# rf_switch.net
KiCad netlist of a schematic drawn in EAGLE
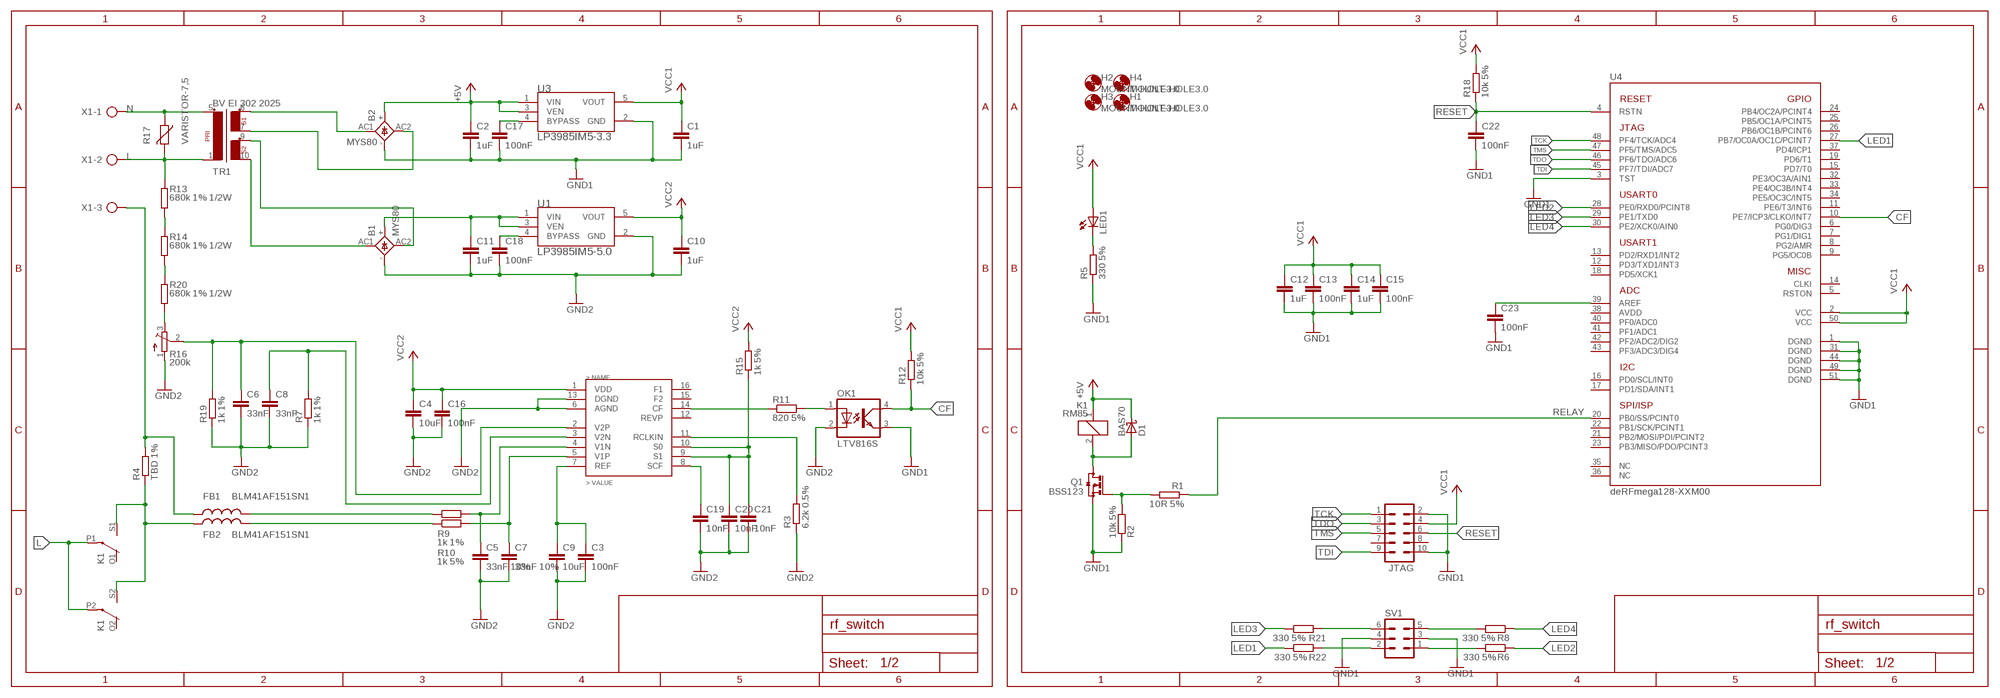
[diagram p0: schematic, sheet 1]

(export (version "E")
  (design (tool "Eeschema 10.0.6"))
  (components
    (comp (ref "B1")
      (value "MYS80")
      (footprint "eagle-import:MICRODIL")
      (libsource (lib "eagle-import") (part "MYS80"))
    )
    (comp (ref "B2")
      (value "MYS80")
      (footprint "eagle-import:MICRODIL")
      (libsource (lib "eagle-import") (part "MYS80"))
    )
    (comp (ref "C1")
      (value "1uF")
      (footprint "eagle-import:C0603")
      (libsource (lib "eagle-import") (part "C-EUC0603"))
    )
    (comp (ref "C2")
      (value "1uF")
      (footprint "eagle-import:C0603")
      (libsource (lib "eagle-import") (part "C-EUC0603"))
    )
    (comp (ref "C3")
      (value "100nF")
      (footprint "eagle-import:C0603")
      (libsource (lib "eagle-import") (part "C-EUC0603"))
    )
    (comp (ref "C4")
      (value "10uF")
      (footprint "eagle-import:C0805")
      (libsource (lib "eagle-import") (part "C-EUC0805"))
    )
    (comp (ref "C5")
      (value "33nF 10%")
      (footprint "eagle-import:C0805")
      (libsource (lib "eagle-import") (part "C-EUC0805"))
    )
    (comp (ref "C6")
      (value "33nF")
      (footprint "eagle-import:C0603")
      (libsource (lib "eagle-import") (part "C-EUC0603"))
    )
    (comp (ref "C7")
      (value "33nF 10%")
      (footprint "eagle-import:C0805")
      (libsource (lib "eagle-import") (part "C-EUC0805"))
    )
    (comp (ref "C8")
      (value "33nF")
      (footprint "eagle-import:C0603")
      (libsource (lib "eagle-import") (part "C-EUC0603"))
    )
    (comp (ref "C9")
      (value "10uF")
      (footprint "eagle-import:C0805")
      (libsource (lib "eagle-import") (part "C-EUC0805"))
    )
    (comp (ref "C10")
      (value "1uF")
      (footprint "eagle-import:C0603")
      (libsource (lib "eagle-import") (part "C-EUC0603"))
    )
    (comp (ref "C11")
      (value "1uF")
      (footprint "eagle-import:C0603")
      (libsource (lib "eagle-import") (part "C-EUC0603"))
    )
    (comp (ref "C12")
      (value "1uF")
      (footprint "eagle-import:C0603")
      (libsource (lib "eagle-import") (part "C-EUC0603"))
    )
    (comp (ref "C13")
      (value "100nF")
      (footprint "eagle-import:C0603")
      (libsource (lib "eagle-import") (part "C-EUC0603"))
    )
    (comp (ref "C14")
      (value "1uF")
      (footprint "eagle-import:C0603")
      (libsource (lib "eagle-import") (part "C-EUC0603"))
    )
    (comp (ref "C15")
      (value "100nF")
      (footprint "eagle-import:C0603")
      (libsource (lib "eagle-import") (part "C-EUC0603"))
    )
    (comp (ref "C16")
      (value "100nF")
      (footprint "eagle-import:C0603")
      (libsource (lib "eagle-import") (part "C-EUC0603"))
    )
    (comp (ref "C17")
      (value "100nF")
      (footprint "eagle-import:C0603")
      (libsource (lib "eagle-import") (part "C-EUC0603"))
    )
    (comp (ref "C18")
      (value "100nF")
      (footprint "eagle-import:C0603")
      (libsource (lib "eagle-import") (part "C-EUC0603"))
    )
    (comp (ref "C19")
      (value "10nF")
      (footprint "eagle-import:C0603")
      (libsource (lib "eagle-import") (part "C-EUC0603"))
    )
    (comp (ref "C20")
      (value "10nF")
      (footprint "eagle-import:C0603")
      (libsource (lib "eagle-import") (part "C-EUC0603"))
    )
    (comp (ref "C21")
      (value "10nF")
      (footprint "eagle-import:C0603")
      (libsource (lib "eagle-import") (part "C-EUC0603"))
    )
    (comp (ref "C22")
      (value "100nF")
      (footprint "eagle-import:C0603")
      (libsource (lib "eagle-import") (part "C-EUC0603"))
    )
    (comp (ref "C23")
      (value "100nF")
      (footprint "eagle-import:C0603")
      (libsource (lib "eagle-import") (part "C-EUC0603"))
    )
    (comp (ref "D1")
      (value "BAS70")
      (footprint "eagle-import:SOT23")
      (libsource (lib "eagle-import") (part "BAS70"))
    )
    (comp (ref "FB1")
      (value "BLM41AF151SN1")
      (footprint "eagle-import:1806")
      (libsource (lib "eagle-import") (part "FERRITE-BEAD"))
    )
    (comp (ref "FB2")
      (value "BLM41AF151SN1")
      (footprint "eagle-import:1806")
      (libsource (lib "eagle-import") (part "FERRITE-BEAD"))
    )
    (comp (ref "H1")
      (value "MOUNT-HOLE3.0")
      (footprint "eagle-import:3,0")
      (libsource (lib "eagle-import") (part "MOUNT-HOLE3.0"))
    )
    (comp (ref "H2")
      (value "MOUNT-HOLE3.0")
      (footprint "eagle-import:3,0")
      (libsource (lib "eagle-import") (part "MOUNT-HOLE3.0"))
    )
    (comp (ref "H3")
      (value "MOUNT-HOLE3.0")
      (footprint "eagle-import:3,0")
      (libsource (lib "eagle-import") (part "MOUNT-HOLE3.0"))
    )
    (comp (ref "H4")
      (value "MOUNT-HOLE3.0")
      (footprint "eagle-import:3,0")
      (libsource (lib "eagle-import") (part "MOUNT-HOLE3.0"))
    )
    (comp (ref "JTAG")
      (value "MA05-2")
      (footprint "eagle-import:MA05-2")
      (libsource (lib "eagle-import") (part "MA05-2"))
    )
    (comp (ref "K1")
      (value "RM85")
      (footprint "eagle-import:F4052")
      (libsource (lib "eagle-import") (part "4052"))
    )
    (comp (ref "LED1")
      (value "LEDSML0603")
      (footprint "eagle-import:SML0603")
      (libsource (lib "eagle-import") (part "LEDSML0603"))
    )
    (comp (ref "OK1")
      (value "LTV816S")
      (footprint "eagle-import:SMD4")
      (libsource (lib "eagle-import") (part "LTV816S"))
    )
    (comp (ref "Q1")
      (value "BSS123")
      (footprint "eagle-import:SOT23")
      (libsource (lib "eagle-import") (part "BSS123"))
    )
    (comp (ref "R1")
      (value "10R 5%")
      (footprint "eagle-import:R0603")
      (libsource (lib "eagle-import") (part "R-EU_R0603"))
    )
    (comp (ref "R2")
      (value "10k 5%")
      (footprint "eagle-import:R0603")
      (libsource (lib "eagle-import") (part "R-EU_R0603"))
    )
    (comp (ref "R3")
      (value "6.2k 0.5%")
      (footprint "eagle-import:R0603")
      (libsource (lib "eagle-import") (part "R-EU_R0603"))
    )
    (comp (ref "R4")
      (value "TBD 1%")
      (footprint "eagle-import:R1206")
      (libsource (lib "eagle-import") (part "R-EU_R1206"))
    )
    (comp (ref "R5")
      (value "330 5%")
      (footprint "eagle-import:R0603")
      (libsource (lib "eagle-import") (part "R-EU_R0603"))
    )
    (comp (ref "R6")
      (value "330 5%")
      (footprint "eagle-import:R0603")
      (libsource (lib "eagle-import") (part "R-EU_R0603"))
    )
    (comp (ref "R7")
      (value "1k 1%")
      (footprint "eagle-import:R0603")
      (libsource (lib "eagle-import") (part "R-EU_R0603"))
    )
    (comp (ref "R8")
      (value "330 5%")
      (footprint "eagle-import:R0603")
      (libsource (lib "eagle-import") (part "R-EU_R0603"))
    )
    (comp (ref "R9")
      (value "1k 1%")
      (footprint "eagle-import:R1206")
      (libsource (lib "eagle-import") (part "R-EU_R1206"))
    )
    (comp (ref "R10")
      (value "1k 5%")
      (footprint "eagle-import:R1206")
      (libsource (lib "eagle-import") (part "R-EU_R1206"))
    )
    (comp (ref "R11")
      (value "820 5%")
      (footprint "eagle-import:R0603")
      (libsource (lib "eagle-import") (part "R-EU_R0603"))
    )
    (comp (ref "R12")
      (value "10k 5%")
      (footprint "eagle-import:R0603")
      (libsource (lib "eagle-import") (part "R-EU_R0603"))
    )
    (comp (ref "R13")
      (value "680k 1% 1/2W")
      (footprint "eagle-import:R1206")
      (libsource (lib "eagle-import") (part "R-EU_R1206"))
    )
    (comp (ref "R14")
      (value "680k 1% 1/2W")
      (footprint "eagle-import:R1206")
      (libsource (lib "eagle-import") (part "R-EU_R1206"))
    )
    (comp (ref "R15")
      (value "1k 5%")
      (footprint "eagle-import:R0603")
      (libsource (lib "eagle-import") (part "R-EU_R0603"))
    )
    (comp (ref "R16")
      (value "200k")
      (footprint "eagle-import:3223W")
      (libsource (lib "eagle-import") (part "TRIM_EU-3223W"))
    )
    (comp (ref "R17")
      (value "VARISTOR-7,5")
      (footprint "eagle-import:R-7,5")
      (libsource (lib "eagle-import") (part "VARISTOR-7,5"))
    )
    (comp (ref "R18")
      (value "10k 5%")
      (footprint "eagle-import:R0603")
      (libsource (lib "eagle-import") (part "R-EU_R0603"))
    )
    (comp (ref "R19")
      (value "1k 1%")
      (footprint "eagle-import:R0603")
      (libsource (lib "eagle-import") (part "R-EU_R0603"))
    )
    (comp (ref "R20")
      (value "680k 1% 1/2W")
      (footprint "eagle-import:R1206")
      (libsource (lib "eagle-import") (part "R-EU_R1206"))
    )
    (comp (ref "R21")
      (value "330 5%")
      (footprint "eagle-import:R0603")
      (libsource (lib "eagle-import") (part "R-EU_R0603"))
    )
    (comp (ref "R22")
      (value "330 5%")
      (footprint "eagle-import:R0603")
      (libsource (lib "eagle-import") (part "R-EU_R0603"))
    )
    (comp (ref "SV1")
      (value "MA03-2")
      (footprint "eagle-import:MA03-2")
      (libsource (lib "eagle-import") (part "MA03-2"))
    )
    (comp (ref "TR1")
      (value "BV EI 302 2025")
      (footprint "eagle-import:EI30-2")
      (libsource (lib "eagle-import") (part "EI30-2"))
    )
    (comp (ref "U1")
      (value "LP3985IM5-5.0")
      (footprint "eagle-import:SOT95P300X120-5N")
      (fields (field (name "MPN") "LP3985IM5-3.3"))
      (libsource (lib "eagle-import") (part "LP3985IM5-3.3"))
    )
    (comp (ref "U2")
      (value "ADE7757")
      (footprint "eagle-import:SOIC-16")
      (libsource (lib "eagle-import") (part "ADE7757"))
    )
    (comp (ref "U3")
      (value "LP3985IM5-3.3")
      (footprint "eagle-import:SOT95P300X120-5N")
      (libsource (lib "eagle-import") (part "LP3985IM5-3.3"))
    )
    (comp (ref "U4")
      (value "DERFMEGA128-XXM00")
      (footprint "eagle-import:A-M00")
      (libsource (lib "eagle-import") (part "DERFMEGA128-XXM00"))
    )
    (comp (ref "X1")
      (value "AK500/3")
      (footprint "eagle-import:AK500_3")
      (libsource (lib "eagle-import") (part "AK500/3"))
    )
  )
  (nets
    (net (code "1") (name "+5V") (class "Default")
      (node (ref "B2") (pin "+") (pinfunction "+_+") (pintype "passive"))
      (node (ref "C2") (pin "1") (pinfunction "1_1") (pintype "passive"))
      (node (ref "D1") (pin "3") (pinfunction "C_3") (pintype "passive"))
      (node (ref "K1") (pin "1") (pinfunction "1_1") (pintype "passive"))
      (node (ref "U3") (pin "1") (pinfunction "VIN_1") (pintype "power_in"))
      (node (ref "U3") (pin "3") (pinfunction "VEN_3") (pintype "input"))
    )
    (net (code "2") (name "AVDD") (class "Default")
      (node (ref "U4") (pin "38") (pinfunction "AVDD_38") (pintype "power_in"))
    )
    (net (code "3") (name "CF") (class "Default")
      (node (ref "OK1") (pin "4") (pinfunction "COL_4") (pintype "passive"))
      (node (ref "R12") (pin "1") (pinfunction "1_1") (pintype "passive"))
      (node (ref "U4") (pin "10") (pinfunction "PE7/ICP3/CLKO/INT7_10") (pintype "bidirectional"))
    )
    (net (code "4") (name "GND1") (class "Default")
      (node (ref "B2") (pin "-") (pinfunction "-_-") (pintype "passive"))
      (node (ref "C1") (pin "2") (pinfunction "2_2") (pintype "passive"))
      (node (ref "C12") (pin "2") (pinfunction "2_2") (pintype "passive"))
      (node (ref "C13") (pin "2") (pinfunction "2_2") (pintype "passive"))
      (node (ref "C14") (pin "2") (pinfunction "2_2") (pintype "passive"))
      (node (ref "C15") (pin "2") (pinfunction "2_2") (pintype "passive"))
      (node (ref "C17") (pin "2") (pinfunction "2_2") (pintype "passive"))
      (node (ref "C2") (pin "2") (pinfunction "2_2") (pintype "passive"))
      (node (ref "C22") (pin "2") (pinfunction "2_2") (pintype "passive"))
      (node (ref "C23") (pin "2") (pinfunction "2_2") (pintype "passive"))
      (node (ref "JTAG") (pin "10") (pinfunction "10_10") (pintype "passive"))
      (node (ref "JTAG") (pin "2") (pinfunction "2_2") (pintype "passive"))
      (node (ref "OK1") (pin "3") (pinfunction "EMIT_3") (pintype "passive"))
      (node (ref "Q1") (pin "2") (pinfunction "S_2") (pintype "passive"))
      (node (ref "R2") (pin "1") (pinfunction "1_1") (pintype "passive"))
      (node (ref "R5") (pin "1") (pinfunction "1_1") (pintype "passive"))
      (node (ref "SV1") (pin "3") (pinfunction "3_3") (pintype "passive"))
      (node (ref "SV1") (pin "4") (pinfunction "4_4") (pintype "passive"))
      (node (ref "U3") (pin "2") (pinfunction "GND_2") (pintype "passive"))
      (node (ref "U4") (pin "1") (pinfunction "DGND_1") (pintype "power_in"))
      (node (ref "U4") (pin "3") (pinfunction "TST_3") (pintype "bidirectional"))
      (node (ref "U4") (pin "31") (pinfunction "DGND_31") (pintype "power_in"))
      (node (ref "U4") (pin "44") (pinfunction "DGND_44") (pintype "power_in"))
      (node (ref "U4") (pin "49") (pinfunction "DGND_49") (pintype "power_in"))
      (node (ref "U4") (pin "51") (pinfunction "DGND_51") (pintype "power_in"))
    )
    (net (code "5") (name "GND2") (class "Default")
      (node (ref "B1") (pin "-") (pinfunction "-_-") (pintype "passive"))
      (node (ref "C10") (pin "2") (pinfunction "2_2") (pintype "passive"))
      (node (ref "C11") (pin "2") (pinfunction "2_2") (pintype "passive"))
      (node (ref "C16") (pin "2") (pinfunction "2_2") (pintype "passive"))
      (node (ref "C18") (pin "2") (pinfunction "2_2") (pintype "passive"))
      (node (ref "C19") (pin "2") (pinfunction "2_2") (pintype "passive"))
      (node (ref "C20") (pin "2") (pinfunction "2_2") (pintype "passive"))
      (node (ref "C21") (pin "2") (pinfunction "2_2") (pintype "passive"))
      (node (ref "C3") (pin "2") (pinfunction "2_2") (pintype "passive"))
      (node (ref "C4") (pin "2") (pinfunction "2_2") (pintype "passive"))
      (node (ref "C5") (pin "2") (pinfunction "2_2") (pintype "passive"))
      (node (ref "C6") (pin "2") (pinfunction "2_2") (pintype "passive"))
      (node (ref "C7") (pin "2") (pinfunction "2_2") (pintype "passive"))
      (node (ref "C8") (pin "2") (pinfunction "2_2") (pintype "passive"))
      (node (ref "C9") (pin "2") (pinfunction "2_2") (pintype "passive"))
      (node (ref "OK1") (pin "2") (pinfunction "C_2") (pintype "passive"))
      (node (ref "R16") (pin "1") (pinfunction "A_1") (pintype "passive"))
      (node (ref "R19") (pin "1") (pinfunction "1_1") (pintype "passive"))
      (node (ref "R3") (pin "1") (pinfunction "1_1") (pintype "passive"))
      (node (ref "R7") (pin "1") (pinfunction "1_1") (pintype "passive"))
      (node (ref "U1") (pin "2") (pinfunction "GND_2") (pintype "passive"))
      (node (ref "U2") (pin "13") (pinfunction "DGND_13") (pintype "power_in"))
      (node (ref "U2") (pin "6") (pinfunction "AGND_6") (pintype "power_in"))
    )
    (net (code "6") (name "L") (class "Default")
      (node (ref "K1") (pin "P1") (pinfunction "P_P1") (pintype "passive"))
      (node (ref "K1") (pin "P2") (pinfunction "P_P2") (pintype "passive"))
      (node (ref "R13") (pin "1") (pinfunction "1_1") (pintype "passive"))
      (node (ref "R17") (pin "2") (pinfunction "2_2") (pintype "passive"))
      (node (ref "TR1") (pin "1") (pinfunction "1_1") (pintype "passive"))
      (node (ref "X1") (pin "2") (pinfunction "KL_2") (pintype "passive"))
    )
    (net (code "7") (name "LED1") (class "Default")
      (node (ref "R22") (pin "1") (pinfunction "1_1") (pintype "passive"))
      (node (ref "U4") (pin "27") (pinfunction "PB7/OC0A/OC1C/PCINT7_27") (pintype "bidirectional"))
    )
    (net (code "8") (name "LED2") (class "Default")
      (node (ref "R6") (pin "1") (pinfunction "1_1") (pintype "passive"))
      (node (ref "U4") (pin "28") (pinfunction "PE0/RXD0/PCINT8_28") (pintype "bidirectional"))
    )
    (net (code "9") (name "LED3") (class "Default")
      (node (ref "R21") (pin "1") (pinfunction "1_1") (pintype "passive"))
      (node (ref "U4") (pin "29") (pinfunction "PE1/TXD0_29") (pintype "bidirectional"))
    )
    (net (code "10") (name "LED4") (class "Default")
      (node (ref "R8") (pin "1") (pinfunction "1_1") (pintype "passive"))
      (node (ref "U4") (pin "30") (pinfunction "PE2/XCK0/AIN0_30") (pintype "bidirectional"))
    )
    (net (code "11") (name "N") (class "Default")
      (node (ref "R17") (pin "1") (pinfunction "1_1") (pintype "passive"))
      (node (ref "TR1") (pin "5") (pinfunction "2_5") (pintype "passive"))
      (node (ref "X1") (pin "1") (pinfunction "KL_1") (pintype "passive"))
    )
    (net (code "12") (name "Net-(D1-A)") (class "Default")
      (node (ref "D1") (pin "1") (pinfunction "A_1") (pintype "passive"))
      (node (ref "K1") (pin "2") (pinfunction "2_2") (pintype "passive"))
      (node (ref "Q1") (pin "3") (pinfunction "D_3") (pintype "passive"))
    )
    (net (code "13") (name "Net-(FB1-1)") (class "Default")
      (node (ref "FB1") (pin "P$1") (pinfunction "1_P$1") (pintype "passive"))
      (node (ref "R4") (pin "2") (pinfunction "2_2") (pintype "passive"))
      (node (ref "X1") (pin "3") (pinfunction "KL_3") (pintype "passive"))
    )
    (net (code "14") (name "Net-(FB1-2)") (class "Default")
      (node (ref "FB1") (pin "P$2") (pinfunction "2_P$2") (pintype "passive"))
      (node (ref "R9") (pin "1") (pinfunction "1_1") (pintype "passive"))
    )
    (net (code "15") (name "Net-(FB2-1)") (class "Default")
      (node (ref "FB2") (pin "P$1") (pinfunction "1_P$1") (pintype "passive"))
      (node (ref "K1") (pin "S1") (pinfunction "S_S1") (pintype "passive"))
      (node (ref "K1") (pin "S2") (pinfunction "S_S2") (pintype "passive"))
      (node (ref "R4") (pin "1") (pinfunction "1_1") (pintype "passive"))
    )
    (net (code "16") (name "Net-(FB2-2)") (class "Default")
      (node (ref "FB2") (pin "P$2") (pinfunction "2_P$2") (pintype "passive"))
      (node (ref "R10") (pin "1") (pinfunction "1_1") (pintype "passive"))
    )
    (net (code "17") (name "Net-(LED1-PadC)") (class "Default")
      (node (ref "LED1") (pin "C") (pinfunction "C_C") (pintype "passive"))
      (node (ref "R5") (pin "2") (pinfunction "2_2") (pintype "passive"))
    )
    (net (code "18") (name "Net-(OK1-A)") (class "Default")
      (node (ref "OK1") (pin "1") (pinfunction "A_1") (pintype "passive"))
      (node (ref "R11") (pin "2") (pinfunction "2_2") (pintype "passive"))
    )
    (net (code "19") (name "Net-(Q1-G)") (class "Default")
      (node (ref "Q1") (pin "1") (pinfunction "G_1") (pintype "passive"))
      (node (ref "R1") (pin "2") (pinfunction "2_2") (pintype "passive"))
      (node (ref "R2") (pin "2") (pinfunction "2_2") (pintype "passive"))
    )
    (net (code "20") (name "Net-(R6-Pad2)") (class "Default")
      (node (ref "R6") (pin "2") (pinfunction "2_2") (pintype "passive"))
      (node (ref "SV1") (pin "1") (pinfunction "1_1") (pintype "passive"))
    )
    (net (code "21") (name "Net-(R8-Pad2)") (class "Default")
      (node (ref "R8") (pin "2") (pinfunction "2_2") (pintype "passive"))
      (node (ref "SV1") (pin "5") (pinfunction "5_5") (pintype "passive"))
    )
    (net (code "22") (name "Net-(R13-Pad2)") (class "Default")
      (node (ref "R13") (pin "2") (pinfunction "2_2") (pintype "passive"))
      (node (ref "R14") (pin "1") (pinfunction "1_1") (pintype "passive"))
    )
    (net (code "23") (name "Net-(R14-Pad2)") (class "Default")
      (node (ref "R14") (pin "2") (pinfunction "2_2") (pintype "passive"))
      (node (ref "R20") (pin "1") (pinfunction "1_1") (pintype "passive"))
    )
    (net (code "24") (name "Net-(R16-E)") (class "Default")
      (node (ref "R16") (pin "3") (pinfunction "E_3") (pintype "passive"))
      (node (ref "R20") (pin "2") (pinfunction "2_2") (pintype "passive"))
    )
    (net (code "25") (name "Net-(R16-S)") (class "Default")
      (node (ref "C6") (pin "1") (pinfunction "1_1") (pintype "passive"))
      (node (ref "R16") (pin "2") (pinfunction "S_2") (pintype "passive"))
      (node (ref "R19") (pin "2") (pinfunction "2_2") (pintype "passive"))
      (node (ref "U2") (pin "2") (pinfunction "V2P_2") (pintype "input"))
    )
    (net (code "26") (name "Net-(R21-Pad2)") (class "Default")
      (node (ref "R21") (pin "2") (pinfunction "2_2") (pintype "passive"))
      (node (ref "SV1") (pin "6") (pinfunction "6_6") (pintype "passive"))
    )
    (net (code "27") (name "Net-(R22-Pad2)") (class "Default")
      (node (ref "R22") (pin "2") (pinfunction "2_2") (pintype "passive"))
      (node (ref "SV1") (pin "2") (pinfunction "2_2") (pintype "passive"))
    )
    (net (code "28") (name "Net-(TR1-3)") (class "Default")
      (node (ref "B2") (pin "AC1") (pinfunction "AC1_AC1") (pintype "passive"))
      (node (ref "TR1") (pin "6") (pinfunction "3_6") (pintype "passive"))
    )
    (net (code "29") (name "Net-(TR1-4)") (class "Default")
      (node (ref "B2") (pin "AC2") (pinfunction "AC2_AC2") (pintype "passive"))
      (node (ref "TR1") (pin "7") (pinfunction "4_7") (pintype "passive"))
    )
    (net (code "30") (name "Net-(TR1-5)") (class "Default")
      (node (ref "B1") (pin "AC2") (pinfunction "AC2_AC2") (pintype "passive"))
      (node (ref "TR1") (pin "9") (pinfunction "5_9") (pintype "passive"))
    )
    (net (code "31") (name "Net-(TR1-6)") (class "Default")
      (node (ref "B1") (pin "AC1") (pinfunction "AC1_AC1") (pintype "passive"))
      (node (ref "TR1") (pin "10") (pinfunction "6_10") (pintype "passive"))
    )
    (net (code "32") (name "Net-(U1-BYPASS)") (class "Default")
      (node (ref "C18") (pin "1") (pinfunction "1_1") (pintype "passive"))
      (node (ref "U1") (pin "4") (pinfunction "BYPASS_4") (pintype "input"))
    )
    (net (code "33") (name "Net-(U1-VEN)") (class "Default")
      (node (ref "B1") (pin "+") (pinfunction "+_+") (pintype "passive"))
      (node (ref "C11") (pin "1") (pinfunction "1_1") (pintype "passive"))
      (node (ref "U1") (pin "1") (pinfunction "VIN_1") (pintype "power_in"))
      (node (ref "U1") (pin "3") (pinfunction "VEN_3") (pintype "input"))
    )
    (net (code "34") (name "Net-(U2-CF)") (class "Default")
      (node (ref "R11") (pin "1") (pinfunction "1_1") (pintype "passive"))
      (node (ref "U2") (pin "14") (pinfunction "CF_14") (pintype "output"))
    )
    (net (code "35") (name "Net-(U2-RCLKIN)") (class "Default")
      (node (ref "R3") (pin "2") (pinfunction "2_2") (pintype "passive"))
      (node (ref "U2") (pin "11") (pinfunction "RCLKIN_11") (pintype "bidirectional"))
    )
    (net (code "36") (name "Net-(U2-REF)") (class "Default")
      (node (ref "C3") (pin "1") (pinfunction "1_1") (pintype "passive"))
      (node (ref "C9") (pin "1") (pinfunction "1_1") (pintype "passive"))
      (node (ref "U2") (pin "7") (pinfunction "REF_7") (pintype "power_in"))
    )
    (net (code "37") (name "Net-(U2-S0)") (class "Default")
      (node (ref "C20") (pin "1") (pinfunction "1_1") (pintype "passive"))
      (node (ref "C21") (pin "1") (pinfunction "1_1") (pintype "passive"))
      (node (ref "R15") (pin "1") (pinfunction "1_1") (pintype "passive"))
      (node (ref "U2") (pin "10") (pinfunction "S0_10") (pintype "input"))
      (node (ref "U2") (pin "9") (pinfunction "S1_9") (pintype "input"))
    )
    (net (code "38") (name "Net-(U2-SCF)") (class "Default")
      (node (ref "C19") (pin "1") (pinfunction "1_1") (pintype "passive"))
      (node (ref "U2") (pin "8") (pinfunction "SCF_8") (pintype "input"))
    )
    (net (code "39") (name "Net-(U2-V1N)") (class "Default")
      (node (ref "C5") (pin "1") (pinfunction "1_1") (pintype "passive"))
      (node (ref "R9") (pin "2") (pinfunction "2_2") (pintype "passive"))
      (node (ref "U2") (pin "4") (pinfunction "V1N_4") (pintype "input"))
    )
    (net (code "40") (name "Net-(U2-V1P)") (class "Default")
      (node (ref "C7") (pin "1") (pinfunction "1_1") (pintype "passive"))
      (node (ref "R10") (pin "2") (pinfunction "2_2") (pintype "passive"))
      (node (ref "U2") (pin "5") (pinfunction "V1P_5") (pintype "input"))
    )
    (net (code "41") (name "Net-(U2-V2N)") (class "Default")
      (node (ref "C8") (pin "1") (pinfunction "1_1") (pintype "passive"))
      (node (ref "R7") (pin "2") (pinfunction "2_2") (pintype "passive"))
      (node (ref "U2") (pin "3") (pinfunction "V2N_3") (pintype "input"))
    )
    (net (code "42") (name "Net-(U3-BYPASS)") (class "Default")
      (node (ref "C17") (pin "1") (pinfunction "1_1") (pintype "passive"))
      (node (ref "U3") (pin "4") (pinfunction "BYPASS_4") (pintype "input"))
    )
    (net (code "43") (name "Net-(U4-AREF)") (class "Default")
      (node (ref "C23") (pin "1") (pinfunction "1_1") (pintype "passive"))
      (node (ref "U4") (pin "39") (pinfunction "AREF_39") (pintype "bidirectional"))
    )
    (net (code "44") (name "RELAY") (class "Default")
      (node (ref "R1") (pin "1") (pinfunction "1_1") (pintype "passive"))
      (node (ref "U4") (pin "20") (pinfunction "PB0/SS/PCINT0_20") (pintype "bidirectional"))
    )
    (net (code "45") (name "RESET") (class "Default")
      (node (ref "C22") (pin "1") (pinfunction "1_1") (pintype "passive"))
      (node (ref "JTAG") (pin "6") (pinfunction "6_6") (pintype "passive"))
      (node (ref "R18") (pin "1") (pinfunction "1_1") (pintype "passive"))
      (node (ref "U4") (pin "4") (pinfunction "RSTN_4") (pintype "input"))
    )
    (net (code "46") (name "TCK") (class "Default")
      (node (ref "JTAG") (pin "1") (pinfunction "1_1") (pintype "passive"))
      (node (ref "U4") (pin "48") (pinfunction "PF4/TCK/ADC4_48") (pintype "bidirectional"))
    )
    (net (code "47") (name "TDI") (class "Default")
      (node (ref "JTAG") (pin "9") (pinfunction "9_9") (pintype "passive"))
      (node (ref "U4") (pin "45") (pinfunction "PF7/TDI/ADC7_45") (pintype "bidirectional"))
    )
    (net (code "48") (name "TDO") (class "Default")
      (node (ref "JTAG") (pin "3") (pinfunction "3_3") (pintype "passive"))
      (node (ref "U4") (pin "46") (pinfunction "PF6/TDO/ADC6_46") (pintype "bidirectional"))
    )
    (net (code "49") (name "TMS") (class "Default")
      (node (ref "JTAG") (pin "5") (pinfunction "5_5") (pintype "passive"))
      (node (ref "U4") (pin "47") (pinfunction "PF5/TMS/ADC5_47") (pintype "bidirectional"))
    )
    (net (code "50") (name "VCC1") (class "Default")
      (node (ref "C1") (pin "1") (pinfunction "1_1") (pintype "passive"))
      (node (ref "C12") (pin "1") (pinfunction "1_1") (pintype "passive"))
      (node (ref "C13") (pin "1") (pinfunction "1_1") (pintype "passive"))
      (node (ref "C14") (pin "1") (pinfunction "1_1") (pintype "passive"))
      (node (ref "C15") (pin "1") (pinfunction "1_1") (pintype "passive"))
      (node (ref "JTAG") (pin "4") (pinfunction "4_4") (pintype "passive"))
      (node (ref "LED1") (pin "A") (pinfunction "A_A") (pintype "passive"))
      (node (ref "R12") (pin "2") (pinfunction "2_2") (pintype "passive"))
      (node (ref "R18") (pin "2") (pinfunction "2_2") (pintype "passive"))
      (node (ref "U3") (pin "5") (pinfunction "VOUT_5") (pintype "output"))
      (node (ref "U4") (pin "2") (pinfunction "VCC_2") (pintype "power_in"))
      (node (ref "U4") (pin "50") (pinfunction "VCC_50") (pintype "power_in"))
    )
    (net (code "51") (name "VCC2") (class "Default")
      (node (ref "C10") (pin "1") (pinfunction "1_1") (pintype "passive"))
      (node (ref "C16") (pin "1") (pinfunction "1_1") (pintype "passive"))
      (node (ref "C4") (pin "1") (pinfunction "1_1") (pintype "passive"))
      (node (ref "R15") (pin "2") (pinfunction "2_2") (pintype "passive"))
      (node (ref "U1") (pin "5") (pinfunction "VOUT_5") (pintype "output"))
      (node (ref "U2") (pin "1") (pinfunction "VDD_1") (pintype "power_in"))
    )
    (net (code "52") (name "unconnected-(JTAG-Pad7)") (class "Default")
      (node (ref "JTAG") (pin "7") (pinfunction "7_7") (pintype "passive"))
    )
    (net (code "53") (name "unconnected-(JTAG-Pad8)") (class "Default")
      (node (ref "JTAG") (pin "8") (pinfunction "8_8") (pintype "passive"))
    )
    (net (code "54") (name "unconnected-(K1B-O-PadO1)") (class "Default")
      (node (ref "K1") (pin "O1") (pinfunction "O_O1") (pintype "passive"))
    )
    (net (code "55") (name "unconnected-(K1C-O-PadO2)") (class "Default")
      (node (ref "K1") (pin "O2") (pinfunction "O_O2") (pintype "passive"))
    )
    (net (code "56") (name "unconnected-(U2-F1-Pad16)") (class "Default")
      (node (ref "U2") (pin "16") (pinfunction "F1_16") (pintype "output"))
    )
    (net (code "57") (name "unconnected-(U2-F2-Pad15)") (class "Default")
      (node (ref "U2") (pin "15") (pinfunction "F2_15") (pintype "output"))
    )
    (net (code "58") (name "unconnected-(U2-REVP-Pad12)") (class "Default")
      (node (ref "U2") (pin "12") (pinfunction "REVP_12") (pintype "output"))
    )
    (net (code "59") (name "unconnected-(U4-CLKI-Pad14)") (class "Default")
      (node (ref "U4") (pin "14") (pinfunction "CLKI_14") (pintype "input"))
    )
    (net (code "60") (name "unconnected-(U4-NC-Pad35)") (class "Default")
      (node (ref "U4") (pin "35") (pinfunction "NC_35") (pintype "no_connect"))
    )
    (net (code "61") (name "unconnected-(U4-NC-Pad36)") (class "Default")
      (node (ref "U4") (pin "36") (pinfunction "NC_36") (pintype "no_connect"))
    )
    (net (code "62") (name "unconnected-(U4-PB1{slash}SCK{slash}PCINT1-Pad22)") (class "Default")
      (node (ref "U4") (pin "22") (pinfunction "PB1/SCK/PCINT1_22") (pintype "bidirectional"))
    )
    (net (code "63") (name "unconnected-(U4-PB2{slash}MOSI{slash}PDI{slash}PCINT2-Pad21)") (class "Default")
      (node (ref "U4") (pin "21") (pinfunction "PB2/MOSI/PDI/PCINT2_21") (pintype "bidirectional"))
    )
    (net (code "64") (name "unconnected-(U4-PB3{slash}MISO{slash}PDO{slash}PCINT3-Pad23)") (class "Default")
      (node (ref "U4") (pin "23") (pinfunction "PB3/MISO/PDO/PCINT3_23") (pintype "bidirectional"))
    )
    (net (code "65") (name "unconnected-(U4-PB4{slash}OC2A{slash}PCINT4-Pad24)") (class "Default")
      (node (ref "U4") (pin "24") (pinfunction "PB4/OC2A/PCINT4_24") (pintype "bidirectional"))
    )
    (net (code "66") (name "unconnected-(U4-PB5{slash}OC1A{slash}PCINT5-Pad25)") (class "Default")
      (node (ref "U4") (pin "25") (pinfunction "PB5/OC1A/PCINT5_25") (pintype "bidirectional"))
    )
    (net (code "67") (name "unconnected-(U4-PB6{slash}OC1B{slash}PCINT6-Pad26)") (class "Default")
      (node (ref "U4") (pin "26") (pinfunction "PB6/OC1B/PCINT6_26") (pintype "bidirectional"))
    )
    (net (code "68") (name "unconnected-(U4-PD0{slash}SCL{slash}INT0-Pad16)") (class "Default")
      (node (ref "U4") (pin "16") (pinfunction "PD0/SCL/INT0_16") (pintype "bidirectional"))
    )
    (net (code "69") (name "unconnected-(U4-PD1{slash}SDA{slash}INT1-Pad17)") (class "Default")
      (node (ref "U4") (pin "17") (pinfunction "PD1/SDA/INT1_17") (pintype "bidirectional"))
    )
    (net (code "70") (name "unconnected-(U4-PD2{slash}RXD1{slash}INT2-Pad13)") (class "Default")
      (node (ref "U4") (pin "13") (pinfunction "PD2/RXD1/INT2_13") (pintype "bidirectional"))
    )
    (net (code "71") (name "unconnected-(U4-PD3{slash}TXD1{slash}INT3-Pad12)") (class "Default")
      (node (ref "U4") (pin "12") (pinfunction "PD3/TXD1/INT3_12") (pintype "bidirectional"))
    )
    (net (code "72") (name "unconnected-(U4-PD4{slash}ICP1-Pad37)") (class "Default")
      (node (ref "U4") (pin "37") (pinfunction "PD4/ICP1_37") (pintype "bidirectional"))
    )
    (net (code "73") (name "unconnected-(U4-PD5{slash}XCK1-Pad18)") (class "Default")
      (node (ref "U4") (pin "18") (pinfunction "PD5/XCK1_18") (pintype "bidirectional"))
    )
    (net (code "74") (name "unconnected-(U4-PD6{slash}T1-Pad19)") (class "Default")
      (node (ref "U4") (pin "19") (pinfunction "PD6/T1_19") (pintype "bidirectional"))
    )
    (net (code "75") (name "unconnected-(U4-PD7{slash}T0-Pad15)") (class "Default")
      (node (ref "U4") (pin "15") (pinfunction "PD7/T0_15") (pintype "bidirectional"))
    )
    (net (code "76") (name "unconnected-(U4-PE3{slash}OC3A{slash}AIN1-Pad32)") (class "Default")
      (node (ref "U4") (pin "32") (pinfunction "PE3/OC3A/AIN1_32") (pintype "bidirectional"))
    )
    (net (code "77") (name "unconnected-(U4-PE4{slash}OC3B{slash}INT4-Pad33)") (class "Default")
      (node (ref "U4") (pin "33") (pinfunction "PE4/OC3B/INT4_33") (pintype "bidirectional"))
    )
    (net (code "78") (name "unconnected-(U4-PE5{slash}OC3C{slash}INT5-Pad34)") (class "Default")
      (node (ref "U4") (pin "34") (pinfunction "PE5/OC3C/INT5_34") (pintype "bidirectional"))
    )
    (net (code "79") (name "unconnected-(U4-PE6{slash}T3{slash}INT6-Pad11)") (class "Default")
      (node (ref "U4") (pin "11") (pinfunction "PE6/T3/INT6_11") (pintype "bidirectional"))
    )
    (net (code "80") (name "unconnected-(U4-PF0{slash}ADC0-Pad40)") (class "Default")
      (node (ref "U4") (pin "40") (pinfunction "PF0/ADC0_40") (pintype "bidirectional"))
    )
    (net (code "81") (name "unconnected-(U4-PF1{slash}ADC1-Pad41)") (class "Default")
      (node (ref "U4") (pin "41") (pinfunction "PF1/ADC1_41") (pintype "bidirectional"))
    )
    (net (code "82") (name "unconnected-(U4-PF2{slash}ADC2{slash}DIG2-Pad42)") (class "Default")
      (node (ref "U4") (pin "42") (pinfunction "PF2/ADC2/DIG2_42") (pintype "bidirectional"))
    )
    (net (code "83") (name "unconnected-(U4-PF3{slash}ADC3{slash}DIG4-Pad43)") (class "Default")
      (node (ref "U4") (pin "43") (pinfunction "PF3/ADC3/DIG4_43") (pintype "bidirectional"))
    )
    (net (code "84") (name "unconnected-(U4-PG0{slash}DIG3-Pad6)") (class "Default")
      (node (ref "U4") (pin "6") (pinfunction "PG0/DIG3_6") (pintype "bidirectional"))
    )
    (net (code "85") (name "unconnected-(U4-PG1{slash}DIG1-Pad7)") (class "Default")
      (node (ref "U4") (pin "7") (pinfunction "PG1/DIG1_7") (pintype "bidirectional"))
    )
    (net (code "86") (name "unconnected-(U4-PG2{slash}AMR-Pad8)") (class "Default")
      (node (ref "U4") (pin "8") (pinfunction "PG2/AMR_8") (pintype "bidirectional"))
    )
    (net (code "87") (name "unconnected-(U4-PG5{slash}OC0B-Pad9)") (class "Default")
      (node (ref "U4") (pin "9") (pinfunction "PG5/OC0B_9") (pintype "bidirectional"))
    )
    (net (code "88") (name "unconnected-(U4-RSTON-Pad5)") (class "Default")
      (node (ref "U4") (pin "5") (pinfunction "RSTON_5") (pintype "output"))
    )
  )
)
